# Filter4.net
KiCad netlist of a schematic drawn in Altium Designer
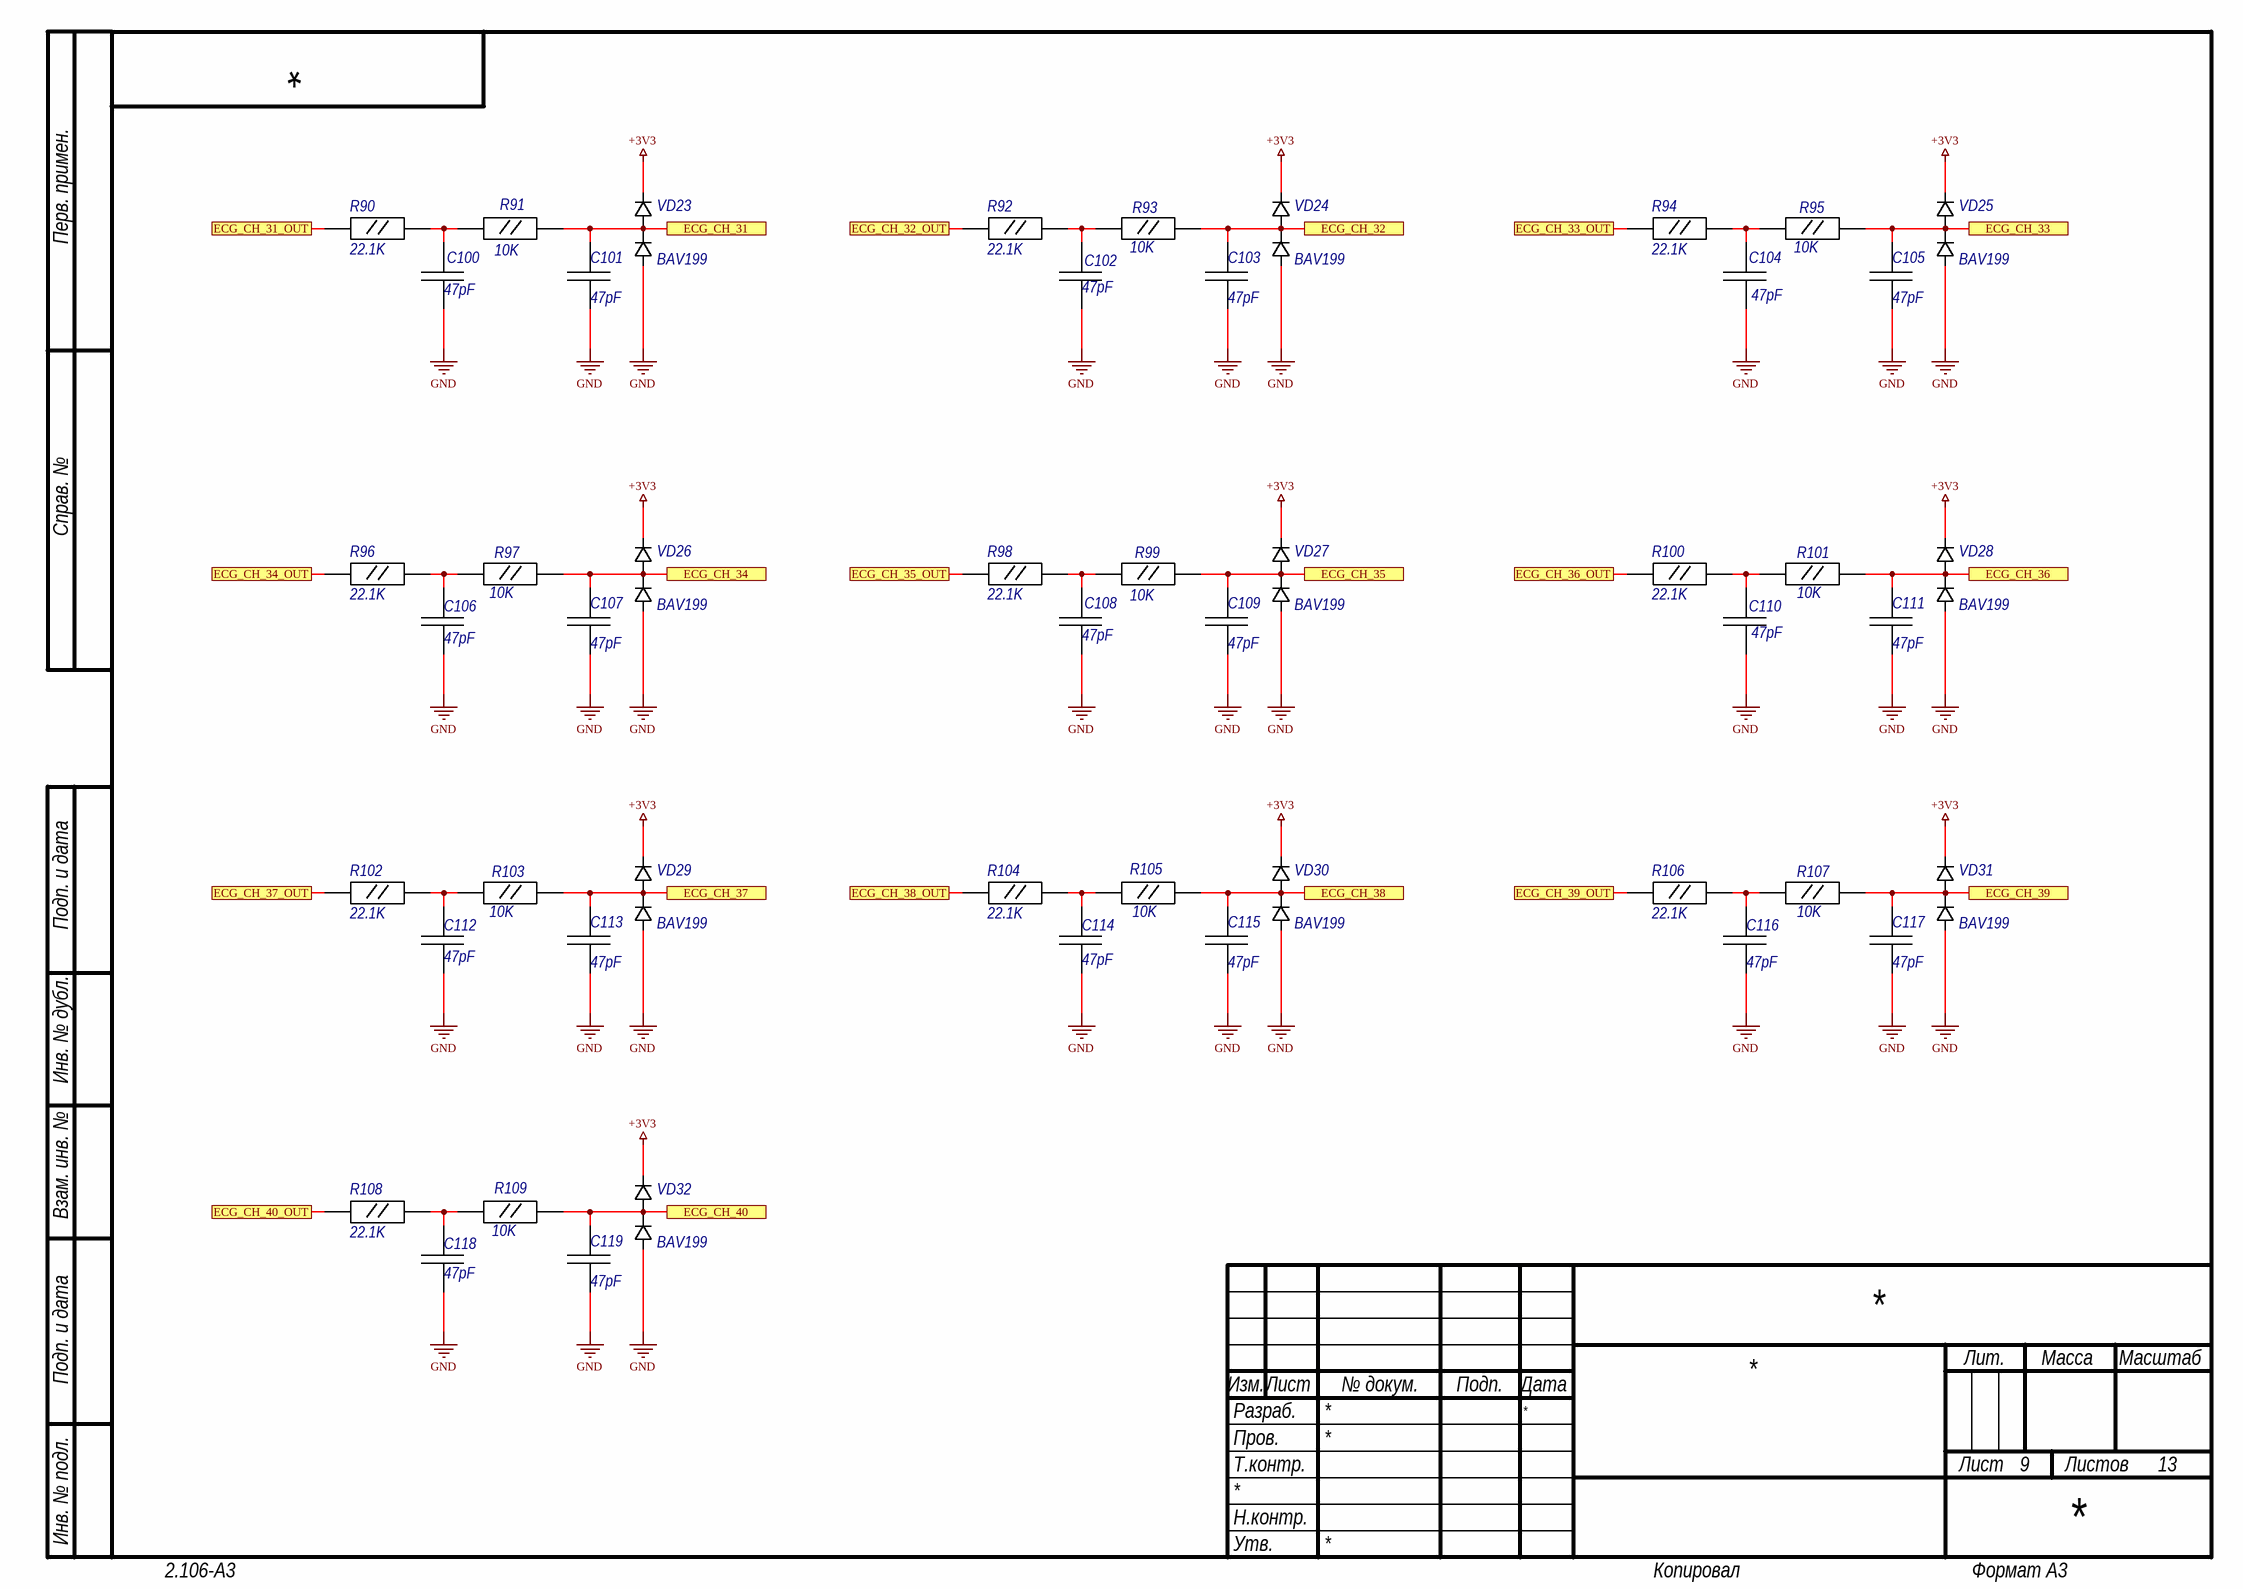
[diagram p0: Filter4.SchDoc]

(export (version "E")
  (design (tool "Eeschema 10.0.6"))
  (components
    (comp (ref "C100")
      (value "47pF")
      (footprint "C0603")
      (description "Ceramic Capacitor SMD")
      (libsource (lib "GOST") (part "CC_SMD_0603"))
    )
    (comp (ref "C101")
      (value "47pF")
      (footprint "C0603")
      (description "Ceramic Capacitor SMD")
      (libsource (lib "GOST") (part "CC_SMD_0603"))
    )
    (comp (ref "C102")
      (value "47pF")
      (footprint "C0603")
      (description "Ceramic Capacitor SMD")
      (libsource (lib "GOST") (part "CC_SMD_0603"))
    )
    (comp (ref "C103")
      (value "47pF")
      (footprint "C0603")
      (description "Ceramic Capacitor SMD")
      (libsource (lib "GOST") (part "CC_SMD_0603"))
    )
    (comp (ref "C104")
      (value "47pF")
      (footprint "C0603")
      (description "Ceramic Capacitor SMD")
      (libsource (lib "GOST") (part "CC_SMD_0603"))
    )
    (comp (ref "C105")
      (value "47pF")
      (footprint "C0603")
      (description "Ceramic Capacitor SMD")
      (libsource (lib "GOST") (part "CC_SMD_0603"))
    )
    (comp (ref "C106")
      (value "47pF")
      (footprint "C0603")
      (description "Ceramic Capacitor SMD")
      (libsource (lib "GOST") (part "CC_SMD_0603"))
    )
    (comp (ref "C107")
      (value "47pF")
      (footprint "C0603")
      (description "Ceramic Capacitor SMD")
      (libsource (lib "GOST") (part "CC_SMD_0603"))
    )
    (comp (ref "C108")
      (value "47pF")
      (footprint "C0603")
      (description "Ceramic Capacitor SMD")
      (libsource (lib "GOST") (part "CC_SMD_0603"))
    )
    (comp (ref "C109")
      (value "47pF")
      (footprint "C0603")
      (description "Ceramic Capacitor SMD")
      (libsource (lib "GOST") (part "CC_SMD_0603"))
    )
    (comp (ref "C110")
      (value "47pF")
      (footprint "C0603")
      (description "Ceramic Capacitor SMD")
      (libsource (lib "GOST") (part "CC_SMD_0603"))
    )
    (comp (ref "C111")
      (value "47pF")
      (footprint "C0603")
      (description "Ceramic Capacitor SMD")
      (libsource (lib "GOST") (part "CC_SMD_0603"))
    )
    (comp (ref "C112")
      (value "47pF")
      (footprint "C0603")
      (description "Ceramic Capacitor SMD")
      (libsource (lib "GOST") (part "CC_SMD_0603"))
    )
    (comp (ref "C113")
      (value "47pF")
      (footprint "C0603")
      (description "Ceramic Capacitor SMD")
      (libsource (lib "GOST") (part "CC_SMD_0603"))
    )
    (comp (ref "C114")
      (value "47pF")
      (footprint "C0603")
      (description "Ceramic Capacitor SMD")
      (libsource (lib "GOST") (part "CC_SMD_0603"))
    )
    (comp (ref "C115")
      (value "47pF")
      (footprint "C0603")
      (description "Ceramic Capacitor SMD")
      (libsource (lib "GOST") (part "CC_SMD_0603"))
    )
    (comp (ref "C116")
      (value "47pF")
      (footprint "C0603")
      (description "Ceramic Capacitor SMD")
      (libsource (lib "GOST") (part "CC_SMD_0603"))
    )
    (comp (ref "C117")
      (value "47pF")
      (footprint "C0603")
      (description "Ceramic Capacitor SMD")
      (libsource (lib "GOST") (part "CC_SMD_0603"))
    )
    (comp (ref "C118")
      (value "47pF")
      (footprint "C0603")
      (description "Ceramic Capacitor SMD")
      (libsource (lib "GOST") (part "CC_SMD_0603"))
    )
    (comp (ref "C119")
      (value "47pF")
      (footprint "C0603")
      (description "Ceramic Capacitor SMD")
      (libsource (lib "GOST") (part "CC_SMD_0603"))
    )
    (comp (ref "R90")
      (value "22.1K")
      (footprint "R0603")
      (description "Resistor SMD")
      (libsource (lib "GOST") (part "R0603"))
    )
    (comp (ref "R91")
      (value "10K")
      (footprint "R0603")
      (description "Resistor SMD")
      (libsource (lib "GOST") (part "R0603"))
    )
    (comp (ref "R92")
      (value "22.1K")
      (footprint "R0603")
      (description "Resistor SMD")
      (libsource (lib "GOST") (part "R0603"))
    )
    (comp (ref "R93")
      (value "10K")
      (footprint "R0603")
      (description "Resistor SMD")
      (libsource (lib "GOST") (part "R0603"))
    )
    (comp (ref "R94")
      (value "22.1K")
      (footprint "R0603")
      (description "Resistor SMD")
      (libsource (lib "GOST") (part "R0603"))
    )
    (comp (ref "R95")
      (value "10K")
      (footprint "R0603")
      (description "Resistor SMD")
      (libsource (lib "GOST") (part "R0603"))
    )
    (comp (ref "R96")
      (value "22.1K")
      (footprint "R0603")
      (description "Resistor SMD")
      (libsource (lib "GOST") (part "R0603"))
    )
    (comp (ref "R97")
      (value "10K")
      (footprint "R0603")
      (description "Resistor SMD")
      (libsource (lib "GOST") (part "R0603"))
    )
    (comp (ref "R98")
      (value "22.1K")
      (footprint "R0603")
      (description "Resistor SMD")
      (libsource (lib "GOST") (part "R0603"))
    )
    (comp (ref "R99")
      (value "10K")
      (footprint "R0603")
      (description "Resistor SMD")
      (libsource (lib "GOST") (part "R0603"))
    )
    (comp (ref "R100")
      (value "22.1K")
      (footprint "R0603")
      (description "Resistor SMD")
      (libsource (lib "GOST") (part "R0603"))
    )
    (comp (ref "R101")
      (value "10K")
      (footprint "R0603")
      (description "Resistor SMD")
      (libsource (lib "GOST") (part "R0603"))
    )
    (comp (ref "R102")
      (value "22.1K")
      (footprint "R0603")
      (description "Resistor SMD")
      (libsource (lib "GOST") (part "R0603"))
    )
    (comp (ref "R103")
      (value "10K")
      (footprint "R0603")
      (description "Resistor SMD")
      (libsource (lib "GOST") (part "R0603"))
    )
    (comp (ref "R104")
      (value "22.1K")
      (footprint "R0603")
      (description "Resistor SMD")
      (libsource (lib "GOST") (part "R0603"))
    )
    (comp (ref "R105")
      (value "10K")
      (footprint "R0603")
      (description "Resistor SMD")
      (libsource (lib "GOST") (part "R0603"))
    )
    (comp (ref "R106")
      (value "22.1K")
      (footprint "R0603")
      (description "Resistor SMD")
      (libsource (lib "GOST") (part "R0603"))
    )
    (comp (ref "R107")
      (value "10K")
      (footprint "R0603")
      (description "Resistor SMD")
      (libsource (lib "GOST") (part "R0603"))
    )
    (comp (ref "R108")
      (value "22.1K")
      (footprint "R0603")
      (description "Resistor SMD")
      (libsource (lib "GOST") (part "R0603"))
    )
    (comp (ref "R109")
      (value "10K")
      (footprint "R0603")
      (description "Resistor SMD")
      (libsource (lib "GOST") (part "R0603"))
    )
    (comp (ref "VD23")
      (value "BAV199")
      (footprint "SOT23")
      (description "Diod Schottky")
      (fields (field (name "MANUFACTURER PART NUMBER 1") "BAV199"))
      (libsource (lib "GOST") (part "DIODE_BAV199"))
    )
    (comp (ref "VD24")
      (value "BAV199")
      (footprint "SOT23")
      (description "Diod Schottky")
      (fields (field (name "MANUFACTURER PART NUMBER 1") "BAV199"))
      (libsource (lib "GOST") (part "DIODE_BAV199"))
    )
    (comp (ref "VD25")
      (value "BAV199")
      (footprint "SOT23")
      (description "Diod Schottky")
      (fields (field (name "MANUFACTURER PART NUMBER 1") "BAV199"))
      (libsource (lib "GOST") (part "DIODE_BAV199"))
    )
    (comp (ref "VD26")
      (value "BAV199")
      (footprint "SOT23")
      (description "Diod Schottky")
      (fields (field (name "MANUFACTURER PART NUMBER 1") "BAV199"))
      (libsource (lib "GOST") (part "DIODE_BAV199"))
    )
    (comp (ref "VD27")
      (value "BAV199")
      (footprint "SOT23")
      (description "Diod Schottky")
      (fields (field (name "MANUFACTURER PART NUMBER 1") "BAV199"))
      (libsource (lib "GOST") (part "DIODE_BAV199"))
    )
    (comp (ref "VD28")
      (value "BAV199")
      (footprint "SOT23")
      (description "Diod Schottky")
      (fields (field (name "MANUFACTURER PART NUMBER 1") "BAV199"))
      (libsource (lib "GOST") (part "DIODE_BAV199"))
    )
    (comp (ref "VD29")
      (value "BAV199")
      (footprint "SOT23")
      (description "Diod Schottky")
      (fields (field (name "MANUFACTURER PART NUMBER 1") "BAV199"))
      (libsource (lib "GOST") (part "DIODE_BAV199"))
    )
    (comp (ref "VD30")
      (value "BAV199")
      (footprint "SOT23")
      (description "Diod Schottky")
      (fields (field (name "MANUFACTURER PART NUMBER 1") "BAV199"))
      (libsource (lib "GOST") (part "DIODE_BAV199"))
    )
    (comp (ref "VD31")
      (value "BAV199")
      (footprint "SOT23")
      (description "Diod Schottky")
      (fields (field (name "MANUFACTURER PART NUMBER 1") "BAV199"))
      (libsource (lib "GOST") (part "DIODE_BAV199"))
    )
    (comp (ref "VD32")
      (value "BAV199")
      (footprint "SOT23")
      (description "Diod Schottky")
      (fields (field (name "MANUFACTURER PART NUMBER 1") "BAV199"))
      (libsource (lib "GOST") (part "DIODE_BAV199"))
    )
  )
  (nets
    (net (code "1") (name "+3V3") (class "Default")
      (node (ref "VD23") (pin "2") (pinfunction "2_2") (pintype "passive"))
      (node (ref "VD24") (pin "2") (pinfunction "2_2") (pintype "passive"))
      (node (ref "VD25") (pin "2") (pinfunction "2_2") (pintype "passive"))
      (node (ref "VD26") (pin "2") (pinfunction "2_2") (pintype "passive"))
      (node (ref "VD27") (pin "2") (pinfunction "2_2") (pintype "passive"))
      (node (ref "VD28") (pin "2") (pinfunction "2_2") (pintype "passive"))
      (node (ref "VD29") (pin "2") (pinfunction "2_2") (pintype "passive"))
      (node (ref "VD30") (pin "2") (pinfunction "2_2") (pintype "passive"))
      (node (ref "VD31") (pin "2") (pinfunction "2_2") (pintype "passive"))
      (node (ref "VD32") (pin "2") (pinfunction "2_2") (pintype "passive"))
    )
    (net (code "2") (name "/ECG_CH_31") (class "Default")
      (node (ref "C101") (pin "2") (pinfunction "2_2") (pintype "passive"))
      (node (ref "R91") (pin "2") (pinfunction "2_2") (pintype "passive"))
      (node (ref "VD23") (pin "3") (pinfunction "3_3") (pintype "passive"))
    )
    (net (code "3") (name "/ECG_CH_31_OUT") (class "Default")
      (node (ref "R90") (pin "1") (pinfunction "1_1") (pintype "passive"))
    )
    (net (code "4") (name "/ECG_CH_32") (class "Default")
      (node (ref "C103") (pin "2") (pinfunction "2_2") (pintype "passive"))
      (node (ref "R93") (pin "2") (pinfunction "2_2") (pintype "passive"))
      (node (ref "VD24") (pin "3") (pinfunction "3_3") (pintype "passive"))
    )
    (net (code "5") (name "/ECG_CH_32_OUT") (class "Default")
      (node (ref "R92") (pin "1") (pinfunction "1_1") (pintype "passive"))
    )
    (net (code "6") (name "/ECG_CH_33") (class "Default")
      (node (ref "C105") (pin "2") (pinfunction "2_2") (pintype "passive"))
      (node (ref "R95") (pin "2") (pinfunction "2_2") (pintype "passive"))
      (node (ref "VD25") (pin "3") (pinfunction "3_3") (pintype "passive"))
    )
    (net (code "7") (name "/ECG_CH_33_OUT") (class "Default")
      (node (ref "R94") (pin "1") (pinfunction "1_1") (pintype "passive"))
    )
    (net (code "8") (name "/ECG_CH_34") (class "Default")
      (node (ref "C107") (pin "2") (pinfunction "2_2") (pintype "passive"))
      (node (ref "R97") (pin "2") (pinfunction "2_2") (pintype "passive"))
      (node (ref "VD26") (pin "3") (pinfunction "3_3") (pintype "passive"))
    )
    (net (code "9") (name "/ECG_CH_34_OUT") (class "Default")
      (node (ref "R96") (pin "1") (pinfunction "1_1") (pintype "passive"))
    )
    (net (code "10") (name "/ECG_CH_35") (class "Default")
      (node (ref "C109") (pin "2") (pinfunction "2_2") (pintype "passive"))
      (node (ref "R99") (pin "2") (pinfunction "2_2") (pintype "passive"))
      (node (ref "VD27") (pin "3") (pinfunction "3_3") (pintype "passive"))
    )
    (net (code "11") (name "/ECG_CH_35_OUT") (class "Default")
      (node (ref "R98") (pin "1") (pinfunction "1_1") (pintype "passive"))
    )
    (net (code "12") (name "/ECG_CH_36") (class "Default")
      (node (ref "C111") (pin "2") (pinfunction "2_2") (pintype "passive"))
      (node (ref "R101") (pin "2") (pinfunction "2_2") (pintype "passive"))
      (node (ref "VD28") (pin "3") (pinfunction "3_3") (pintype "passive"))
    )
    (net (code "13") (name "/ECG_CH_36_OUT") (class "Default")
      (node (ref "R100") (pin "1") (pinfunction "1_1") (pintype "passive"))
    )
    (net (code "14") (name "/ECG_CH_37") (class "Default")
      (node (ref "C113") (pin "2") (pinfunction "2_2") (pintype "passive"))
      (node (ref "R103") (pin "2") (pinfunction "2_2") (pintype "passive"))
      (node (ref "VD29") (pin "3") (pinfunction "3_3") (pintype "passive"))
    )
    (net (code "15") (name "/ECG_CH_37_OUT") (class "Default")
      (node (ref "R102") (pin "1") (pinfunction "1_1") (pintype "passive"))
    )
    (net (code "16") (name "/ECG_CH_38") (class "Default")
      (node (ref "C115") (pin "2") (pinfunction "2_2") (pintype "passive"))
      (node (ref "R105") (pin "2") (pinfunction "2_2") (pintype "passive"))
      (node (ref "VD30") (pin "3") (pinfunction "3_3") (pintype "passive"))
    )
    (net (code "17") (name "/ECG_CH_38_OUT") (class "Default")
      (node (ref "R104") (pin "1") (pinfunction "1_1") (pintype "passive"))
    )
    (net (code "18") (name "/ECG_CH_39") (class "Default")
      (node (ref "C117") (pin "2") (pinfunction "2_2") (pintype "passive"))
      (node (ref "R107") (pin "2") (pinfunction "2_2") (pintype "passive"))
      (node (ref "VD31") (pin "3") (pinfunction "3_3") (pintype "passive"))
    )
    (net (code "19") (name "/ECG_CH_39_OUT") (class "Default")
      (node (ref "R106") (pin "1") (pinfunction "1_1") (pintype "passive"))
    )
    (net (code "20") (name "/ECG_CH_40") (class "Default")
      (node (ref "C119") (pin "2") (pinfunction "2_2") (pintype "passive"))
      (node (ref "R109") (pin "2") (pinfunction "2_2") (pintype "passive"))
      (node (ref "VD32") (pin "3") (pinfunction "3_3") (pintype "passive"))
    )
    (net (code "21") (name "/ECG_CH_40_OUT") (class "Default")
      (node (ref "R108") (pin "1") (pinfunction "1_1") (pintype "passive"))
    )
    (net (code "22") (name "GND") (class "Default")
      (node (ref "C100") (pin "1") (pinfunction "1_1") (pintype "passive"))
      (node (ref "C101") (pin "1") (pinfunction "1_1") (pintype "passive"))
      (node (ref "C102") (pin "1") (pinfunction "1_1") (pintype "passive"))
      (node (ref "C103") (pin "1") (pinfunction "1_1") (pintype "passive"))
      (node (ref "C104") (pin "1") (pinfunction "1_1") (pintype "passive"))
      (node (ref "C105") (pin "1") (pinfunction "1_1") (pintype "passive"))
      (node (ref "C106") (pin "1") (pinfunction "1_1") (pintype "passive"))
      (node (ref "C107") (pin "1") (pinfunction "1_1") (pintype "passive"))
      (node (ref "C108") (pin "1") (pinfunction "1_1") (pintype "passive"))
      (node (ref "C109") (pin "1") (pinfunction "1_1") (pintype "passive"))
      (node (ref "C110") (pin "1") (pinfunction "1_1") (pintype "passive"))
      (node (ref "C111") (pin "1") (pinfunction "1_1") (pintype "passive"))
      (node (ref "C112") (pin "1") (pinfunction "1_1") (pintype "passive"))
      (node (ref "C113") (pin "1") (pinfunction "1_1") (pintype "passive"))
      (node (ref "C114") (pin "1") (pinfunction "1_1") (pintype "passive"))
      (node (ref "C115") (pin "1") (pinfunction "1_1") (pintype "passive"))
      (node (ref "C116") (pin "1") (pinfunction "1_1") (pintype "passive"))
      (node (ref "C117") (pin "1") (pinfunction "1_1") (pintype "passive"))
      (node (ref "C118") (pin "1") (pinfunction "1_1") (pintype "passive"))
      (node (ref "C119") (pin "1") (pinfunction "1_1") (pintype "passive"))
      (node (ref "VD23") (pin "1") (pinfunction "1_1") (pintype "passive"))
      (node (ref "VD24") (pin "1") (pinfunction "1_1") (pintype "passive"))
      (node (ref "VD25") (pin "1") (pinfunction "1_1") (pintype "passive"))
      (node (ref "VD26") (pin "1") (pinfunction "1_1") (pintype "passive"))
      (node (ref "VD27") (pin "1") (pinfunction "1_1") (pintype "passive"))
      (node (ref "VD28") (pin "1") (pinfunction "1_1") (pintype "passive"))
      (node (ref "VD29") (pin "1") (pinfunction "1_1") (pintype "passive"))
      (node (ref "VD30") (pin "1") (pinfunction "1_1") (pintype "passive"))
      (node (ref "VD31") (pin "1") (pinfunction "1_1") (pintype "passive"))
      (node (ref "VD32") (pin "1") (pinfunction "1_1") (pintype "passive"))
    )
    (net (code "23") (name "Net-(C100-Pad2)") (class "Default")
      (node (ref "C100") (pin "2") (pinfunction "2_2") (pintype "passive"))
      (node (ref "R90") (pin "2") (pinfunction "2_2") (pintype "passive"))
      (node (ref "R91") (pin "1") (pinfunction "1_1") (pintype "passive"))
    )
    (net (code "24") (name "Net-(C102-Pad2)") (class "Default")
      (node (ref "C102") (pin "2") (pinfunction "2_2") (pintype "passive"))
      (node (ref "R92") (pin "2") (pinfunction "2_2") (pintype "passive"))
      (node (ref "R93") (pin "1") (pinfunction "1_1") (pintype "passive"))
    )
    (net (code "25") (name "Net-(C104-Pad2)") (class "Default")
      (node (ref "C104") (pin "2") (pinfunction "2_2") (pintype "passive"))
      (node (ref "R94") (pin "2") (pinfunction "2_2") (pintype "passive"))
      (node (ref "R95") (pin "1") (pinfunction "1_1") (pintype "passive"))
    )
    (net (code "26") (name "Net-(C106-Pad2)") (class "Default")
      (node (ref "C106") (pin "2") (pinfunction "2_2") (pintype "passive"))
      (node (ref "R96") (pin "2") (pinfunction "2_2") (pintype "passive"))
      (node (ref "R97") (pin "1") (pinfunction "1_1") (pintype "passive"))
    )
    (net (code "27") (name "Net-(C108-Pad2)") (class "Default")
      (node (ref "C108") (pin "2") (pinfunction "2_2") (pintype "passive"))
      (node (ref "R98") (pin "2") (pinfunction "2_2") (pintype "passive"))
      (node (ref "R99") (pin "1") (pinfunction "1_1") (pintype "passive"))
    )
    (net (code "28") (name "Net-(C110-Pad2)") (class "Default")
      (node (ref "C110") (pin "2") (pinfunction "2_2") (pintype "passive"))
      (node (ref "R100") (pin "2") (pinfunction "2_2") (pintype "passive"))
      (node (ref "R101") (pin "1") (pinfunction "1_1") (pintype "passive"))
    )
    (net (code "29") (name "Net-(C112-Pad2)") (class "Default")
      (node (ref "C112") (pin "2") (pinfunction "2_2") (pintype "passive"))
      (node (ref "R102") (pin "2") (pinfunction "2_2") (pintype "passive"))
      (node (ref "R103") (pin "1") (pinfunction "1_1") (pintype "passive"))
    )
    (net (code "30") (name "Net-(C114-Pad2)") (class "Default")
      (node (ref "C114") (pin "2") (pinfunction "2_2") (pintype "passive"))
      (node (ref "R104") (pin "2") (pinfunction "2_2") (pintype "passive"))
      (node (ref "R105") (pin "1") (pinfunction "1_1") (pintype "passive"))
    )
    (net (code "31") (name "Net-(C116-Pad2)") (class "Default")
      (node (ref "C116") (pin "2") (pinfunction "2_2") (pintype "passive"))
      (node (ref "R106") (pin "2") (pinfunction "2_2") (pintype "passive"))
      (node (ref "R107") (pin "1") (pinfunction "1_1") (pintype "passive"))
    )
    (net (code "32") (name "Net-(C118-Pad2)") (class "Default")
      (node (ref "C118") (pin "2") (pinfunction "2_2") (pintype "passive"))
      (node (ref "R108") (pin "2") (pinfunction "2_2") (pintype "passive"))
      (node (ref "R109") (pin "1") (pinfunction "1_1") (pintype "passive"))
    )
  )
)
